# MCUs.net
KiCad netlist of a schematic drawn in Altium Designer
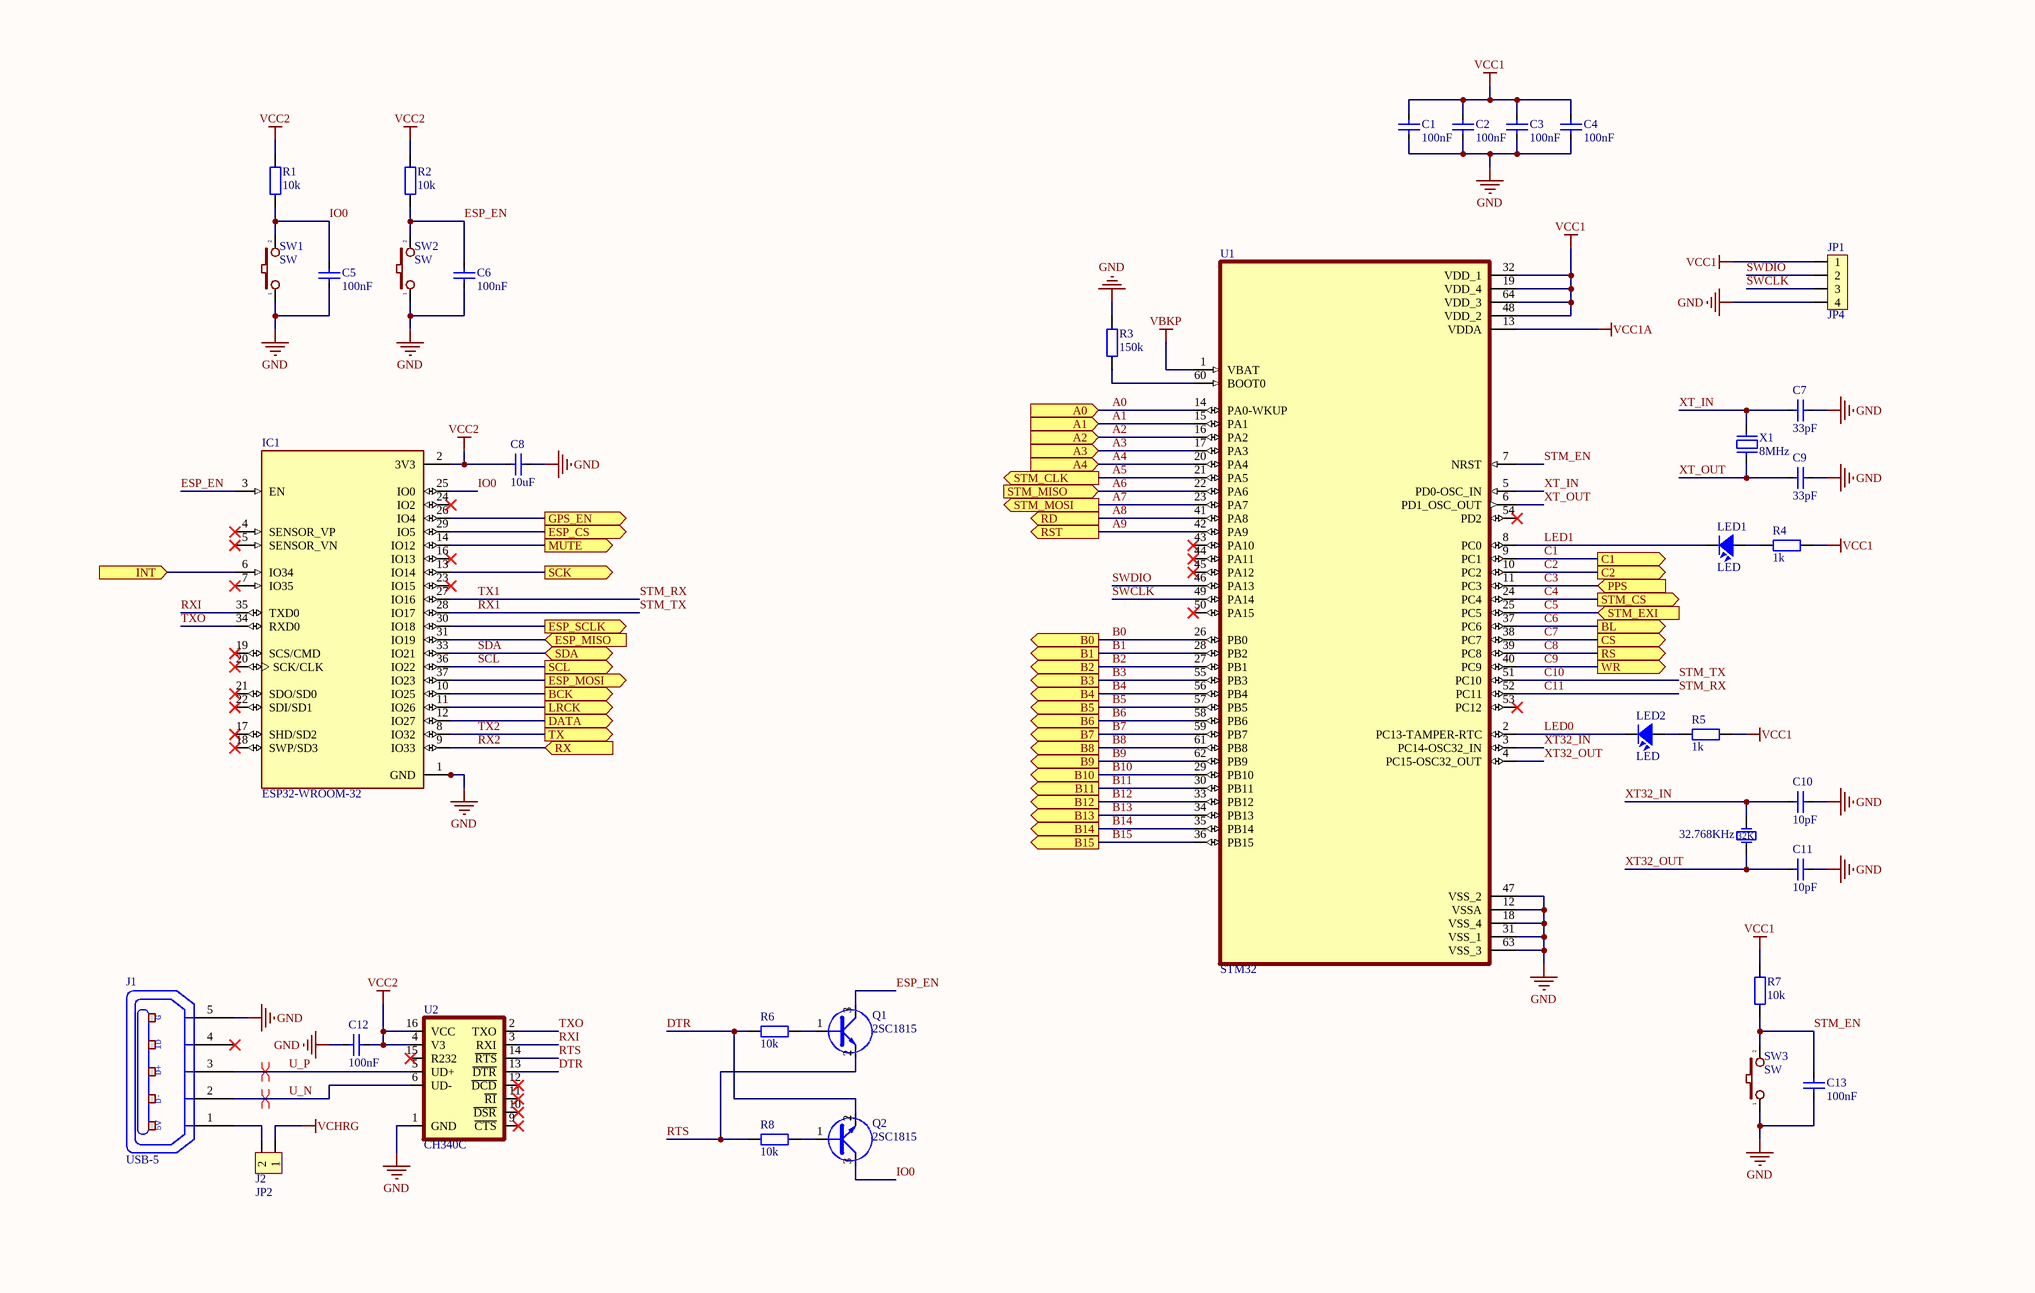
[diagram p0: MCUs.SchDoc]

(export (version "E")
  (design (tool "Eeschema 10.0.6"))
  (components
    (comp (ref "C1")
      (value "100nF")
      (footprint "CAP_0603")
      (description "Capacitor")
      (fields (field (name "PUBLISHER") "Altium Limited"))
      (libsource (lib "My Library") (part "CapSMD"))
    )
    (comp (ref "C2")
      (value "100nF")
      (footprint "CAP_0603")
      (description "Capacitor")
      (fields (field (name "PUBLISHER") "Altium Limited"))
      (libsource (lib "My Library") (part "CapSMD"))
    )
    (comp (ref "C3")
      (value "100nF")
      (footprint "CAP_0603")
      (description "Capacitor")
      (fields (field (name "PUBLISHER") "Altium Limited"))
      (libsource (lib "My Library") (part "CapSMD"))
    )
    (comp (ref "C4")
      (value "100nF")
      (footprint "CAP_0603")
      (description "Capacitor")
      (fields (field (name "PUBLISHER") "Altium Limited"))
      (libsource (lib "My Library") (part "CapSMD"))
    )
    (comp (ref "C5")
      (value "100nF")
      (footprint "CAP_0603")
      (description "Capacitor")
      (fields (field (name "PUBLISHER") "Altium Limited"))
      (libsource (lib "My Library") (part "CapSMD"))
    )
    (comp (ref "C6")
      (value "100nF")
      (footprint "CAP_0603")
      (description "Capacitor")
      (fields (field (name "PUBLISHER") "Altium Limited"))
      (libsource (lib "My Library") (part "CapSMD"))
    )
    (comp (ref "C7")
      (value "33pF")
      (footprint "CAP_0603")
      (description "Capacitor")
      (fields (field (name "PUBLISHER") "Altium Limited"))
      (libsource (lib "My Library") (part "CapSMD"))
    )
    (comp (ref "C8")
      (value "10uF")
      (footprint "CAP_0603")
      (description "Capacitor")
      (fields (field (name "PUBLISHER") "Altium Limited"))
      (libsource (lib "My Library") (part "CapSMD"))
    )
    (comp (ref "C9")
      (value "33pF")
      (footprint "CAP_0603")
      (description "Capacitor")
      (fields (field (name "PUBLISHER") "Altium Limited"))
      (libsource (lib "My Library") (part "CapSMD"))
    )
    (comp (ref "C10")
      (value "10pF")
      (footprint "CAP_0603")
      (description "Capacitor")
      (fields (field (name "PUBLISHER") "Altium Limited"))
      (libsource (lib "My Library") (part "CapSMD"))
    )
    (comp (ref "C11")
      (value "10pF")
      (footprint "CAP_0603")
      (description "Capacitor")
      (fields (field (name "PUBLISHER") "Altium Limited"))
      (libsource (lib "My Library") (part "CapSMD"))
    )
    (comp (ref "C12")
      (value "100nF")
      (footprint "CAP_0603")
      (description "Capacitor")
      (fields (field (name "PUBLISHER") "Altium Limited"))
      (libsource (lib "My Library") (part "CapSMD"))
    )
    (comp (ref "C13")
      (value "100nF")
      (footprint "CAP_0603")
      (description "Capacitor")
      (fields (field (name "PUBLISHER") "Altium Limited"))
      (libsource (lib "My Library") (part "CapSMD"))
    )
    (comp (ref "IC1")
      (value "ESP32-WROOM-32")
      (footprint "MODULE_ESP32-WROOM-32")
      (description "Bluetooth, WiFi Transceiver Module 2.4GHz ~ 2.5GHz Surface Mount")
      (fields (field (name "MF") "Espressif Systems") (field (name "DIGI-KEY_PART_NUMBER") "1904-1010-1-ND"))
      (libsource (lib "My Library") (part "ESP32-WROOM-32"))
    )
    (comp (ref "J1")
      (value "USB-5")
      (footprint "USB-M1")
      (fields
        (field (name "MANUFACTURER") "FCI")
        (field (name "MANUFACTURER PART NUMBER") "10118193-0001LF")
        (field (name ".CREATOR") "MM")
        (field (name ".CHECKED PCB") "RF")
        (field (name ".CHECKED SCH") "MM")
      )
      (libsource (lib "My Library") (part "USB-5"))
    )
    (comp (ref "J2")
      (value "JP2")
      (footprint "JP2-CLOSED")
      (description "WR-PHD 2.54 mm Angled Socket Header")
      (fields
        (field (name "MANUFACTURER") "Würth Elektronik eiSos GmbH")
        (field (name "PARTNO") "613002143121")
        (field (name "CREATED BY") "Karrer Zheng")
      )
      (libsource (lib "My Library") (part "JP2"))
    )
    (comp (ref "JP1")
      (value "JP4")
      (footprint "JP4-C1T")
      (description "WR-PHD 2.54 mm Angled Socket Header")
      (fields
        (field (name "MANUFACTURER") "Würth Elektronik eiSos GmbH")
        (field (name "PARTNO") "613004143121")
        (field (name "CREATED BY") "Karrer Zheng")
      )
      (libsource (lib "My Library") (part "JP4"))
    )
    (comp (ref "LED1")
      (value "LED")
      (footprint "LED-0805-Red")
      (description "LED Single colour Green and Red")
      (libsource (lib "My Library") (part "LED"))
    )
    (comp (ref "LED2")
      (value "LED")
      (footprint "LED-0805-Red")
      (description "LED Single colour Green and Red")
      (libsource (lib "My Library") (part "LED"))
    )
    (comp (ref "Q1")
      (value "2SC1815")
      (footprint "SOT23D")
      (description "NPN 600mW, ECB")
      (libsource (lib "My Library") (part "C1815"))
    )
    (comp (ref "Q2")
      (value "2SC1815")
      (footprint "SOT23D")
      (description "NPN 600mW, ECB")
      (libsource (lib "") (part "C1815_1"))
    )
    (comp (ref "R1")
      (value "10k")
      (footprint "RES-SMD-0603")
      (description "Resistor SMD")
      (fields
        (field (name "MANUFACTURER") "Generic Components")
        (field (name "PUBLISHER") "Altium Hobart Technology Centre")
      )
      (libsource (lib "My Library") (part "Resistor - SMD"))
    )
    (comp (ref "R2")
      (value "10k")
      (footprint "RES-SMD-0603")
      (description "Resistor SMD")
      (fields
        (field (name "MANUFACTURER") "Generic Components")
        (field (name "PUBLISHER") "Altium Hobart Technology Centre")
      )
      (libsource (lib "My Library") (part "Resistor - SMD"))
    )
    (comp (ref "R3")
      (value "150k")
      (footprint "RES-SMD-0603")
      (description "Resistor SMD")
      (fields
        (field (name "MANUFACTURER") "Generic Components")
        (field (name "PUBLISHER") "Altium Hobart Technology Centre")
      )
      (libsource (lib "My Library") (part "Resistor - SMD"))
    )
    (comp (ref "R4")
      (value "1k")
      (footprint "RES-SMD-0603")
      (description "Resistor SMD")
      (fields
        (field (name "MANUFACTURER") "Generic Components")
        (field (name "PUBLISHER") "Altium Hobart Technology Centre")
      )
      (libsource (lib "My Library") (part "Resistor - SMD"))
    )
    (comp (ref "R5")
      (value "1k")
      (footprint "RES-SMD-0603")
      (description "Resistor SMD")
      (fields
        (field (name "MANUFACTURER") "Generic Components")
        (field (name "PUBLISHER") "Altium Hobart Technology Centre")
      )
      (libsource (lib "My Library") (part "Resistor - SMD"))
    )
    (comp (ref "R6")
      (value "10k")
      (footprint "RES-SMD-0603")
      (description "Resistor SMD")
      (fields
        (field (name "MANUFACTURER") "Generic Components")
        (field (name "PUBLISHER") "Altium Hobart Technology Centre")
      )
      (libsource (lib "My Library") (part "Resistor - SMD"))
    )
    (comp (ref "R7")
      (value "10k")
      (footprint "RES-SMD-0603")
      (description "Resistor SMD")
      (fields
        (field (name "MANUFACTURER") "Generic Components")
        (field (name "PUBLISHER") "Altium Hobart Technology Centre")
      )
      (libsource (lib "My Library") (part "Resistor - SMD"))
    )
    (comp (ref "R8")
      (value "10k")
      (footprint "RES-SMD-0603")
      (description "Resistor SMD")
      (fields
        (field (name "MANUFACTURER") "Generic Components")
        (field (name "PUBLISHER") "Altium Hobart Technology Centre")
      )
      (libsource (lib "My Library") (part "Resistor - SMD"))
    )
    (comp (ref "SW1")
      (value "SW")
      (footprint "SW 3x2x4")
      (description "Switch button 2 pin")
      (libsource (lib "My Library") (part "SW2"))
    )
    (comp (ref "SW2")
      (value "SW")
      (footprint "SW 3x2x4")
      (description "Switch button 2 pin")
      (libsource (lib "My Library") (part "SW2"))
    )
    (comp (ref "SW3")
      (value "SW")
      (footprint "SW 3x2x4")
      (description "Switch button 2 pin")
      (libsource (lib "My Library") (part "SW2"))
    )
    (comp (ref "U1")
      (value "STM32")
      (footprint "LQFP 64")
      (description "STM32 ARM-based 32-bit MCU 72MHz 256KB")
      (libsource (lib "My Library") (part "STM32F103RCT6"))
    )
    (comp (ref "U2")
      (value "CH340C")
      (footprint "SOP-16")
      (description "USB to serial chip CH340")
      (fields (field (name "MF") "WCH"))
      (libsource (lib "My Library") (part "CH340C"))
    )
    (comp (ref "X1")
      (value "8MHz")
      (footprint "XT2")
      (description "Crystal For all Crystal 2pin.")
      (libsource (lib "My Library") (part "XT2"))
    )
    (comp (ref "Y1")
      (value "32.768KHz")
      (footprint "XTAL32K")
      (description "Crystal Oscillator")
      (fields (field (name "PUBLISHER") "Altium Limited"))
      (libsource (lib "My Library") (part "XTAL/32KHz"))
    )
  )
  (nets
    (net (code "1") (name "/A0") (class "Default")
      (node (ref "U1") (pin "14") (pinfunction "PA0-WKUP_14") (pintype "bidirectional"))
    )
    (net (code "2") (name "/A1") (class "Default")
      (node (ref "U1") (pin "15") (pinfunction "PA1_15") (pintype "bidirectional"))
    )
    (net (code "3") (name "/A2") (class "Default")
      (node (ref "U1") (pin "16") (pinfunction "PA2_16") (pintype "bidirectional"))
    )
    (net (code "4") (name "/A3") (class "Default")
      (node (ref "U1") (pin "17") (pinfunction "PA3_17") (pintype "bidirectional"))
    )
    (net (code "5") (name "/A4") (class "Default")
      (node (ref "U1") (pin "20") (pinfunction "PA4_20") (pintype "bidirectional"))
    )
    (net (code "6") (name "/A5") (class "Default")
      (node (ref "U1") (pin "21") (pinfunction "PA5_21") (pintype "bidirectional"))
    )
    (net (code "7") (name "/A6") (class "Default")
      (node (ref "U1") (pin "22") (pinfunction "PA6_22") (pintype "bidirectional"))
    )
    (net (code "8") (name "/A7") (class "Default")
      (node (ref "U1") (pin "23") (pinfunction "PA7_23") (pintype "bidirectional"))
    )
    (net (code "9") (name "/A8") (class "Default")
      (node (ref "U1") (pin "41") (pinfunction "PA8_41") (pintype "bidirectional"))
    )
    (net (code "10") (name "/A9") (class "Default")
      (node (ref "U1") (pin "42") (pinfunction "PA9_42") (pintype "bidirectional"))
    )
    (net (code "11") (name "/B0") (class "Default")
      (node (ref "U1") (pin "26") (pinfunction "PB0_26") (pintype "bidirectional"))
    )
    (net (code "12") (name "/B1") (class "Default")
      (node (ref "U1") (pin "28") (pinfunction "PB2_28") (pintype "bidirectional"))
    )
    (net (code "13") (name "/B2") (class "Default")
      (node (ref "U1") (pin "27") (pinfunction "PB1_27") (pintype "bidirectional"))
    )
    (net (code "14") (name "/B3") (class "Default")
      (node (ref "U1") (pin "55") (pinfunction "PB3_55") (pintype "bidirectional"))
    )
    (net (code "15") (name "/B4") (class "Default")
      (node (ref "U1") (pin "56") (pinfunction "PB4_56") (pintype "bidirectional"))
    )
    (net (code "16") (name "/B5") (class "Default")
      (node (ref "U1") (pin "57") (pinfunction "PB5_57") (pintype "bidirectional"))
    )
    (net (code "17") (name "/B6") (class "Default")
      (node (ref "U1") (pin "58") (pinfunction "PB6_58") (pintype "bidirectional"))
    )
    (net (code "18") (name "/B7") (class "Default")
      (node (ref "U1") (pin "59") (pinfunction "PB7_59") (pintype "bidirectional"))
    )
    (net (code "19") (name "/B8") (class "Default")
      (node (ref "U1") (pin "61") (pinfunction "PB8_61") (pintype "bidirectional"))
    )
    (net (code "20") (name "/B9") (class "Default")
      (node (ref "U1") (pin "62") (pinfunction "PB9_62") (pintype "bidirectional"))
    )
    (net (code "21") (name "/B10") (class "Default")
      (node (ref "U1") (pin "29") (pinfunction "PB10_29") (pintype "bidirectional"))
    )
    (net (code "22") (name "/B11") (class "Default")
      (node (ref "U1") (pin "30") (pinfunction "PB11_30") (pintype "bidirectional"))
    )
    (net (code "23") (name "/B12") (class "Default")
      (node (ref "U1") (pin "33") (pinfunction "PB12_33") (pintype "bidirectional"))
    )
    (net (code "24") (name "/B13") (class "Default")
      (node (ref "U1") (pin "34") (pinfunction "PB13_34") (pintype "bidirectional"))
    )
    (net (code "25") (name "/B14") (class "Default")
      (node (ref "U1") (pin "35") (pinfunction "PB14_35") (pintype "bidirectional"))
    )
    (net (code "26") (name "/B15") (class "Default")
      (node (ref "U1") (pin "36") (pinfunction "PB15_36") (pintype "bidirectional"))
    )
    (net (code "27") (name "/BCK") (class "Default")
      (node (ref "IC1") (pin "10") (pinfunction "IO25_10") (pintype "bidirectional"))
    )
    (net (code "28") (name "/C1") (class "Default")
      (node (ref "U1") (pin "9") (pinfunction "PC1_9") (pintype "bidirectional"))
    )
    (net (code "29") (name "/C2") (class "Default")
      (node (ref "U1") (pin "10") (pinfunction "PC2_10") (pintype "bidirectional"))
    )
    (net (code "30") (name "/C3") (class "Default")
      (node (ref "U1") (pin "11") (pinfunction "PC3_11") (pintype "bidirectional"))
    )
    (net (code "31") (name "/C4") (class "Default")
      (node (ref "U1") (pin "24") (pinfunction "PC4_24") (pintype "bidirectional"))
    )
    (net (code "32") (name "/C5") (class "Default")
      (node (ref "U1") (pin "25") (pinfunction "PC5_25") (pintype "bidirectional"))
    )
    (net (code "33") (name "/C6") (class "Default")
      (node (ref "U1") (pin "37") (pinfunction "PC6_37") (pintype "bidirectional"))
    )
    (net (code "34") (name "/C7") (class "Default")
      (node (ref "U1") (pin "38") (pinfunction "PC7_38") (pintype "bidirectional"))
    )
    (net (code "35") (name "/C8") (class "Default")
      (node (ref "U1") (pin "39") (pinfunction "PC8_39") (pintype "bidirectional"))
    )
    (net (code "36") (name "/C9") (class "Default")
      (node (ref "U1") (pin "40") (pinfunction "PC9_40") (pintype "bidirectional"))
    )
    (net (code "37") (name "/C10") (class "Default")
      (node (ref "IC1") (pin "28") (pinfunction "IO17_28") (pintype "bidirectional"))
      (node (ref "U1") (pin "51") (pinfunction "PC10_51") (pintype "bidirectional"))
    )
    (net (code "38") (name "/C11") (class "Default")
      (node (ref "IC1") (pin "27") (pinfunction "IO16_27") (pintype "bidirectional"))
      (node (ref "U1") (pin "52") (pinfunction "PC11_52") (pintype "bidirectional"))
    )
    (net (code "39") (name "/DATA") (class "Default")
      (node (ref "IC1") (pin "12") (pinfunction "IO27_12") (pintype "bidirectional"))
    )
    (net (code "40") (name "/DTR") (class "Default")
      (node (ref "Q2") (pin "2") (pinfunction "E_2") (pintype "passive"))
      (node (ref "R6") (pin "2") (pinfunction "2_2") (pintype "passive"))
      (node (ref "U2") (pin "13") (pinfunction "~{DTR}_13") (pintype "bidirectional"))
    )
    (net (code "41") (name "/ESP_CS") (class "Default")
      (node (ref "IC1") (pin "29") (pinfunction "IO5_29") (pintype "bidirectional"))
    )
    (net (code "42") (name "/ESP_EN") (class "Default")
      (node (ref "C6") (pin "1") (pinfunction "1_1") (pintype "passive"))
      (node (ref "IC1") (pin "3") (pinfunction "EN_3") (pintype "input"))
      (node (ref "Q1") (pin "3") (pinfunction "C_3") (pintype "passive"))
      (node (ref "R2") (pin "1") (pinfunction "1_1") (pintype "passive"))
      (node (ref "SW2") (pin "2") (pinfunction "2_2") (pintype "passive"))
    )
    (net (code "43") (name "/ESP_MISO") (class "Default")
      (node (ref "IC1") (pin "31") (pinfunction "IO19_31") (pintype "bidirectional"))
    )
    (net (code "44") (name "/ESP_MOSI") (class "Default")
      (node (ref "IC1") (pin "37") (pinfunction "IO23_37") (pintype "bidirectional"))
    )
    (net (code "45") (name "/ESP_SCLK") (class "Default")
      (node (ref "IC1") (pin "30") (pinfunction "IO18_30") (pintype "bidirectional"))
    )
    (net (code "46") (name "/GPS_EN") (class "Default")
      (node (ref "IC1") (pin "26") (pinfunction "IO4_26") (pintype "bidirectional"))
    )
    (net (code "47") (name "/INT") (class "Default")
      (node (ref "IC1") (pin "6") (pinfunction "IO34_6") (pintype "input"))
    )
    (net (code "48") (name "/IO0") (class "Default")
      (node (ref "C5") (pin "1") (pinfunction "1_1") (pintype "passive"))
      (node (ref "IC1") (pin "25") (pinfunction "IO0_25") (pintype "bidirectional"))
      (node (ref "Q2") (pin "3") (pinfunction "C_3") (pintype "passive"))
      (node (ref "R1") (pin "1") (pinfunction "1_1") (pintype "passive"))
      (node (ref "SW1") (pin "2") (pinfunction "2_2") (pintype "passive"))
    )
    (net (code "49") (name "/LED0") (class "Default")
      (node (ref "LED2") (pin "2") (pinfunction "2_2") (pintype "passive"))
      (node (ref "U1") (pin "2") (pinfunction "PC13-TAMPER-RTC_2") (pintype "bidirectional"))
    )
    (net (code "50") (name "/LED1") (class "Default")
      (node (ref "LED1") (pin "2") (pinfunction "2_2") (pintype "passive"))
      (node (ref "U1") (pin "8") (pinfunction "PC0_8") (pintype "bidirectional"))
    )
    (net (code "51") (name "/LRCK") (class "Default")
      (node (ref "IC1") (pin "11") (pinfunction "IO26_11") (pintype "bidirectional"))
    )
    (net (code "52") (name "/MUTE") (class "Default")
      (node (ref "IC1") (pin "14") (pinfunction "IO12_14") (pintype "bidirectional"))
    )
    (net (code "53") (name "/RTS") (class "Default")
      (node (ref "Q1") (pin "2") (pinfunction "E_2") (pintype "passive"))
      (node (ref "R8") (pin "2") (pinfunction "2_2") (pintype "passive"))
      (node (ref "U2") (pin "14") (pinfunction "~{RTS}_14") (pintype "bidirectional"))
    )
    (net (code "54") (name "/RX2") (class "Default")
      (node (ref "IC1") (pin "9") (pinfunction "IO33_9") (pintype "bidirectional"))
    )
    (net (code "55") (name "/RXI") (class "Default")
      (node (ref "IC1") (pin "35") (pinfunction "TXD0_35") (pintype "bidirectional"))
      (node (ref "U2") (pin "3") (pinfunction "RXI_3") (pintype "bidirectional"))
    )
    (net (code "56") (name "/SCK") (class "Default")
      (node (ref "IC1") (pin "13") (pinfunction "IO14_13") (pintype "bidirectional"))
    )
    (net (code "57") (name "/SCL") (class "Default")
      (node (ref "IC1") (pin "36") (pinfunction "IO22_36") (pintype "bidirectional"))
    )
    (net (code "58") (name "/SDA") (class "Default")
      (node (ref "IC1") (pin "33") (pinfunction "IO21_33") (pintype "bidirectional"))
    )
    (net (code "59") (name "/STM_EN") (class "Default")
      (node (ref "C13") (pin "1") (pinfunction "1_1") (pintype "passive"))
      (node (ref "R7") (pin "1") (pinfunction "1_1") (pintype "passive"))
      (node (ref "SW3") (pin "2") (pinfunction "2_2") (pintype "passive"))
      (node (ref "U1") (pin "7") (pinfunction "NRST_7") (pintype "input"))
    )
    (net (code "60") (name "/SWCLK") (class "Default")
      (node (ref "JP1") (pin "3") (pinfunction "3_3") (pintype "passive"))
      (node (ref "U1") (pin "49") (pinfunction "PA14_49") (pintype "bidirectional"))
    )
    (net (code "61") (name "/SWDIO") (class "Default")
      (node (ref "JP1") (pin "2") (pinfunction "2_2") (pintype "passive"))
      (node (ref "U1") (pin "46") (pinfunction "PA13_46") (pintype "bidirectional"))
    )
    (net (code "62") (name "/TX2") (class "Default")
      (node (ref "IC1") (pin "8") (pinfunction "IO32_8") (pintype "bidirectional"))
    )
    (net (code "63") (name "/TXO") (class "Default")
      (node (ref "IC1") (pin "34") (pinfunction "RXD0_34") (pintype "bidirectional"))
      (node (ref "U2") (pin "2") (pinfunction "TXO_2") (pintype "bidirectional"))
    )
    (net (code "64") (name "/U_N") (class "Default")
      (node (ref "J1") (pin "2") (pinfunction "P2_2") (pintype "passive"))
      (node (ref "U2") (pin "6") (pinfunction "UD-_6") (pintype "bidirectional"))
    )
    (net (code "65") (name "/U_P") (class "Default")
      (node (ref "J1") (pin "3") (pinfunction "P3_3") (pintype "passive"))
      (node (ref "U2") (pin "5") (pinfunction "UD+_5") (pintype "bidirectional"))
    )
    (net (code "66") (name "/XT32_IN") (class "Default")
      (node (ref "C10") (pin "2") (pinfunction "2_2") (pintype "passive"))
      (node (ref "U1") (pin "3") (pinfunction "PC14-OSC32_IN_3") (pintype "bidirectional"))
      (node (ref "Y1") (pin "1") (pinfunction "OSC1_1") (pintype "passive"))
    )
    (net (code "67") (name "/XT32_OUT") (class "Default")
      (node (ref "C11") (pin "2") (pinfunction "2_2") (pintype "passive"))
      (node (ref "U1") (pin "4") (pinfunction "PC15-OSC32_OUT_4") (pintype "bidirectional"))
      (node (ref "Y1") (pin "2") (pinfunction "OSC2_2") (pintype "passive"))
    )
    (net (code "68") (name "/XT_IN") (class "Default")
      (node (ref "C7") (pin "2") (pinfunction "2_2") (pintype "passive"))
      (node (ref "U1") (pin "5") (pinfunction "PD0-OSC_IN_5") (pintype "input"))
      (node (ref "X1") (pin "2") (pinfunction "2_2") (pintype "passive"))
    )
    (net (code "69") (name "/XT_OUT") (class "Default")
      (node (ref "C9") (pin "2") (pinfunction "2_2") (pintype "passive"))
      (node (ref "U1") (pin "6") (pinfunction "PD1_OSC_OUT_6") (pintype "output"))
      (node (ref "X1") (pin "1") (pinfunction "1_1") (pintype "passive"))
    )
    (net (code "70") (name "GND") (class "Default")
      (node (ref "C1") (pin "2") (pinfunction "2_2") (pintype "passive"))
      (node (ref "C10") (pin "1") (pinfunction "1_1") (pintype "passive"))
      (node (ref "C11") (pin "1") (pinfunction "1_1") (pintype "passive"))
      (node (ref "C12") (pin "1") (pinfunction "1_1") (pintype "passive"))
      (node (ref "C13") (pin "2") (pinfunction "2_2") (pintype "passive"))
      (node (ref "C2") (pin "2") (pinfunction "2_2") (pintype "passive"))
      (node (ref "C3") (pin "2") (pinfunction "2_2") (pintype "passive"))
      (node (ref "C4") (pin "2") (pinfunction "2_2") (pintype "passive"))
      (node (ref "C5") (pin "2") (pinfunction "2_2") (pintype "passive"))
      (node (ref "C6") (pin "2") (pinfunction "2_2") (pintype "passive"))
      (node (ref "C7") (pin "1") (pinfunction "1_1") (pintype "passive"))
      (node (ref "C8") (pin "2") (pinfunction "2_2") (pintype "passive"))
      (node (ref "C9") (pin "1") (pinfunction "1_1") (pintype "passive"))
      (node (ref "IC1") (pin "1") (pinfunction "GND_1") (pintype "power_in"))
      (node (ref "IC1") (pin "15") (pinfunction "GND_15") (pintype "power_in"))
      (node (ref "IC1") (pin "38") (pinfunction "GND_38") (pintype "power_in"))
      (node (ref "IC1") (pin "39_1") (pinfunction "GND_39_1") (pintype "power_in"))
      (node (ref "IC1") (pin "39_10") (pinfunction "GND_39_10") (pintype "power_in"))
      (node (ref "IC1") (pin "39_11") (pinfunction "GND_39_11") (pintype "power_in"))
      (node (ref "IC1") (pin "39_12") (pinfunction "GND_39_12") (pintype "power_in"))
      (node (ref "IC1") (pin "39_13") (pinfunction "GND_39_13") (pintype "power_in"))
      (node (ref "IC1") (pin "39_14") (pinfunction "GND_39_14") (pintype "power_in"))
      (node (ref "IC1") (pin "39_15") (pinfunction "GND_39_15") (pintype "power_in"))
      (node (ref "IC1") (pin "39_16") (pinfunction "GND_39_16") (pintype "power_in"))
      (node (ref "IC1") (pin "39_17") (pinfunction "GND_39_17") (pintype "power_in"))
      (node (ref "IC1") (pin "39_18") (pinfunction "GND_39_18") (pintype "power_in"))
      (node (ref "IC1") (pin "39_19") (pinfunction "GND_39_19") (pintype "power_in"))
      (node (ref "IC1") (pin "39_2") (pinfunction "GND_39_2") (pintype "power_in"))
      (node (ref "IC1") (pin "39_20") (pinfunction "GND_39_20") (pintype "power_in"))
      (node (ref "IC1") (pin "39_21") (pinfunction "GND_39_21") (pintype "power_in"))
      (node (ref "IC1") (pin "39_3") (pinfunction "GND_39_3") (pintype "power_in"))
      (node (ref "IC1") (pin "39_4") (pinfunction "GND_39_4") (pintype "power_in"))
      (node (ref "IC1") (pin "39_5") (pinfunction "GND_39_5") (pintype "power_in"))
      (node (ref "IC1") (pin "39_6") (pinfunction "GND_39_6") (pintype "power_in"))
      (node (ref "IC1") (pin "39_7") (pinfunction "GND_39_7") (pintype "power_in"))
      (node (ref "IC1") (pin "39_8") (pinfunction "GND_39_8") (pintype "power_in"))
      (node (ref "IC1") (pin "39_9") (pinfunction "GND_39_9") (pintype "power_in"))
      (node (ref "J1") (pin "5") (pinfunction "P5_5") (pintype "passive"))
      (node (ref "JP1") (pin "4") (pinfunction "4_4") (pintype "passive"))
      (node (ref "R3") (pin "1") (pinfunction "1_1") (pintype "passive"))
      (node (ref "SW1") (pin "1") (pinfunction "1_1") (pintype "passive"))
      (node (ref "SW2") (pin "1") (pinfunction "1_1") (pintype "passive"))
      (node (ref "SW3") (pin "1") (pinfunction "1_1") (pintype "passive"))
      (node (ref "U1") (pin "12") (pinfunction "VSSA_12") (pintype "power_in"))
      (node (ref "U1") (pin "18") (pinfunction "VSS_4_18") (pintype "power_in"))
      (node (ref "U1") (pin "31") (pinfunction "VSS_1_31") (pintype "power_in"))
      (node (ref "U1") (pin "47") (pinfunction "VSS_2_47") (pintype "power_in"))
      (node (ref "U1") (pin "63") (pinfunction "VSS_3_63") (pintype "power_in"))
      (node (ref "U2") (pin "1") (pinfunction "GND_1") (pintype "bidirectional"))
    )
    (net (code "71") (name "Net-(J1-P1)") (class "Default")
      (node (ref "J1") (pin "1") (pinfunction "P1_1") (pintype "passive"))
      (node (ref "J2") (pin "2") (pinfunction "2_2") (pintype "passive"))
    )
    (net (code "72") (name "Net-(LED1-Pad1)") (class "Default")
      (node (ref "LED1") (pin "1") (pinfunction "1_1") (pintype "passive"))
      (node (ref "R4") (pin "2") (pinfunction "2_2") (pintype "passive"))
    )
    (net (code "73") (name "Net-(LED2-Pad1)") (class "Default")
      (node (ref "LED2") (pin "1") (pinfunction "1_1") (pintype "passive"))
      (node (ref "R5") (pin "2") (pinfunction "2_2") (pintype "passive"))
    )
    (net (code "74") (name "Net-(Q1-B)") (class "Default")
      (node (ref "Q1") (pin "1") (pinfunction "B_1") (pintype "passive"))
      (node (ref "R6") (pin "1") (pinfunction "1_1") (pintype "passive"))
    )
    (net (code "75") (name "Net-(Q2-B)") (class "Default")
      (node (ref "Q2") (pin "1") (pinfunction "B_1") (pintype "passive"))
      (node (ref "R8") (pin "1") (pinfunction "1_1") (pintype "passive"))
    )
    (net (code "76") (name "Net-(U1-BOOT0)") (class "Default")
      (node (ref "R3") (pin "2") (pinfunction "2_2") (pintype "passive"))
      (node (ref "U1") (pin "60") (pinfunction "BOOT0_60") (pintype "input"))
    )
    (net (code "77") (name "VBKP") (class "Default")
      (node (ref "U1") (pin "1") (pinfunction "VBAT_1") (pintype "input"))
    )
    (net (code "78") (name "VCC1") (class "Default")
      (node (ref "C1") (pin "1") (pinfunction "1_1") (pintype "passive"))
      (node (ref "C2") (pin "1") (pinfunction "1_1") (pintype "passive"))
      (node (ref "C3") (pin "1") (pinfunction "1_1") (pintype "passive"))
      (node (ref "C4") (pin "1") (pinfunction "1_1") (pintype "passive"))
      (node (ref "JP1") (pin "1") (pinfunction "1_1") (pintype "passive"))
      (node (ref "R4") (pin "1") (pinfunction "1_1") (pintype "passive"))
      (node (ref "R5") (pin "1") (pinfunction "1_1") (pintype "passive"))
      (node (ref "R7") (pin "2") (pinfunction "2_2") (pintype "passive"))
      (node (ref "U1") (pin "19") (pinfunction "VDD_4_19") (pintype "power_in"))
      (node (ref "U1") (pin "32") (pinfunction "VDD_1_32") (pintype "power_in"))
      (node (ref "U1") (pin "48") (pinfunction "VDD_2_48") (pintype "power_in"))
      (node (ref "U1") (pin "64") (pinfunction "VDD_3_64") (pintype "power_in"))
    )
    (net (code "79") (name "VCC1A") (class "Default")
      (node (ref "U1") (pin "13") (pinfunction "VDDA_13") (pintype "power_in"))
    )
    (net (code "80") (name "VCC2") (class "Default")
      (node (ref "C12") (pin "2") (pinfunction "2_2") (pintype "passive"))
      (node (ref "C8") (pin "1") (pinfunction "1_1") (pintype "passive"))
      (node (ref "IC1") (pin "2") (pinfunction "3V3_2") (pintype "power_in"))
      (node (ref "R1") (pin "2") (pinfunction "2_2") (pintype "passive"))
      (node (ref "R2") (pin "2") (pinfunction "2_2") (pintype "passive"))
      (node (ref "U2") (pin "16") (pinfunction "VCC_16") (pintype "bidirectional"))
      (node (ref "U2") (pin "4") (pinfunction "V3_4") (pintype "bidirectional"))
    )
    (net (code "81") (name "VCHRG") (class "Default")
      (node (ref "J2") (pin "1") (pinfunction "1_1") (pintype "passive"))
    )
    (net (code "82") (name "unconnected-(IC1-IO2-Pad24)") (class "Default")
      (node (ref "IC1") (pin "24") (pinfunction "IO2_24") (pintype "bidirectional+no_connect"))
    )
    (net (code "83") (name "unconnected-(IC1-IO13-Pad16)") (class "Default")
      (node (ref "IC1") (pin "16") (pinfunction "IO13_16") (pintype "bidirectional+no_connect"))
    )
    (net (code "84") (name "unconnected-(IC1-IO15-Pad23)") (class "Default")
      (node (ref "IC1") (pin "23") (pinfunction "IO15_23") (pintype "bidirectional+no_connect"))
    )
    (net (code "85") (name "unconnected-(IC1-IO35-Pad7)") (class "Default")
      (node (ref "IC1") (pin "7") (pinfunction "IO35_7") (pintype "input+no_connect"))
    )
    (net (code "86") (name "unconnected-(IC1-SCK{slash}CLK-Pad20)") (class "Default")
      (node (ref "IC1") (pin "20") (pinfunction "SCK/CLK_20") (pintype "bidirectional+no_connect"))
    )
    (net (code "87") (name "unconnected-(IC1-SCS{slash}CMD-Pad19)") (class "Default")
      (node (ref "IC1") (pin "19") (pinfunction "SCS/CMD_19") (pintype "bidirectional+no_connect"))
    )
    (net (code "88") (name "unconnected-(IC1-SDI{slash}SD1-Pad22)") (class "Default")
      (node (ref "IC1") (pin "22") (pinfunction "SDI/SD1_22") (pintype "bidirectional+no_connect"))
    )
    (net (code "89") (name "unconnected-(IC1-SDO{slash}SD0-Pad21)") (class "Default")
      (node (ref "IC1") (pin "21") (pinfunction "SDO/SD0_21") (pintype "bidirectional+no_connect"))
    )
    (net (code "90") (name "unconnected-(IC1-SENSOR_VN-Pad5)") (class "Default")
      (node (ref "IC1") (pin "5") (pinfunction "SENSOR_VN_5") (pintype "input+no_connect"))
    )
    (net (code "91") (name "unconnected-(IC1-SENSOR_VP-Pad4)") (class "Default")
      (node (ref "IC1") (pin "4") (pinfunction "SENSOR_VP_4") (pintype "input+no_connect"))
    )
    (net (code "92") (name "unconnected-(IC1-SHD{slash}SD2-Pad17)") (class "Default")
      (node (ref "IC1") (pin "17") (pinfunction "SHD/SD2_17") (pintype "bidirectional+no_connect"))
    )
    (net (code "93") (name "unconnected-(IC1-SWP{slash}SD3-Pad18)") (class "Default")
      (node (ref "IC1") (pin "18") (pinfunction "SWP/SD3_18") (pintype "bidirectional+no_connect"))
    )
    (net (code "94") (name "unconnected-(J1-P4-Pad4)") (class "Default")
      (node (ref "J1") (pin "4") (pinfunction "P4_4") (pintype "passive+no_connect"))
    )
    (net (code "95") (name "unconnected-(U1-PA10-Pad43)") (class "Default")
      (node (ref "U1") (pin "43") (pinfunction "PA10_43") (pintype "bidirectional+no_connect"))
    )
    (net (code "96") (name "unconnected-(U1-PA11-Pad44)") (class "Default")
      (node (ref "U1") (pin "44") (pinfunction "PA11_44") (pintype "bidirectional+no_connect"))
    )
    (net (code "97") (name "unconnected-(U1-PA12-Pad45)") (class "Default")
      (node (ref "U1") (pin "45") (pinfunction "PA12_45") (pintype "bidirectional+no_connect"))
    )
    (net (code "98") (name "unconnected-(U1-PA15-Pad50)") (class "Default")
      (node (ref "U1") (pin "50") (pinfunction "PA15_50") (pintype "bidirectional+no_connect"))
    )
    (net (code "99") (name "unconnected-(U1-PC12-Pad53)") (class "Default")
      (node (ref "U1") (pin "53") (pinfunction "PC12_53") (pintype "bidirectional+no_connect"))
    )
    (net (code "100") (name "unconnected-(U1-PD2-Pad54)") (class "Default")
      (node (ref "U1") (pin "54") (pinfunction "PD2_54") (pintype "bidirectional+no_connect"))
    )
    (net (code "101") (name "unconnected-(U2-R232-Pad15)") (class "Default")
      (node (ref "U2") (pin "15") (pinfunction "R232_15") (pintype "bidirectional+no_connect"))
    )
    (net (code "102") (name "unconnected-(U2-~{CTS}-Pad9)") (class "Default")
      (node (ref "U2") (pin "9") (pinfunction "~{CTS}_9") (pintype "bidirectional+no_connect"))
    )
    (net (code "103") (name "unconnected-(U2-~{DCD}-Pad12)") (class "Default")
      (node (ref "U2") (pin "12") (pinfunction "~{DCD}_12") (pintype "bidirectional+no_connect"))
    )
    (net (code "104") (name "unconnected-(U2-~{DSR}-Pad10)") (class "Default")
      (node (ref "U2") (pin "10") (pinfunction "~{DSR}_10") (pintype "bidirectional+no_connect"))
    )
    (net (code "105") (name "unconnected-(U2-~{RI}-Pad11)") (class "Default")
      (node (ref "U2") (pin "11") (pinfunction "~{RI}_11") (pintype "bidirectional+no_connect"))
    )
  )
)
